# SMD_LED_Breakout.net
KiCad netlist of a schematic drawn in EAGLE
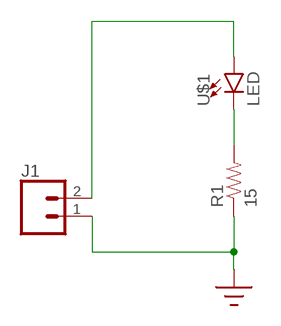
[diagram p0: schematic, sheet 1]

(export (version "E")
  (design (tool "Eeschema 10.0.6"))
  (components
    (comp (ref "J1")
      (value "CONN_02")
      (footprint "eagle-import:1X02")
      (libsource (lib "eagle-import") (part "CONN_02"))
    )
    (comp (ref "R1")
      (value "15")
      (footprint "eagle-import:AXIAL-0.6")
      (libsource (lib "eagle-import") (part "RESISTORPTH-1W"))
    )
    (comp (ref "U$1")
      (value "LED")
      (footprint "eagle-import:VSMY7852X01-GS08")
      (libsource (lib "eagle-import") (part "LED"))
    )
  )
  (nets
    (net (code "1") (name "GND") (class "Default")
      (node (ref "J1") (pin "1") (pinfunction "1_1") (pintype "passive"))
      (node (ref "R1") (pin "P$1") (pinfunction "1_P$1") (pintype "passive"))
    )
    (net (code "2") (name "Net-(R1-2)") (class "Default")
      (node (ref "R1") (pin "P$2") (pinfunction "2_P$2") (pintype "passive"))
      (node (ref "U$1") (pin "-") (pinfunction "C_-") (pintype "passive"))
    )
    (net (code "3") (name "Net-(U$1-A)") (class "Default")
      (node (ref "J1") (pin "2") (pinfunction "2_2") (pintype "passive"))
      (node (ref "U$1") (pin "+") (pinfunction "A_+") (pintype "passive"))
    )
  )
)
